# bus-main.net
KiCad netlist of a schematic drawn in Altium Designer
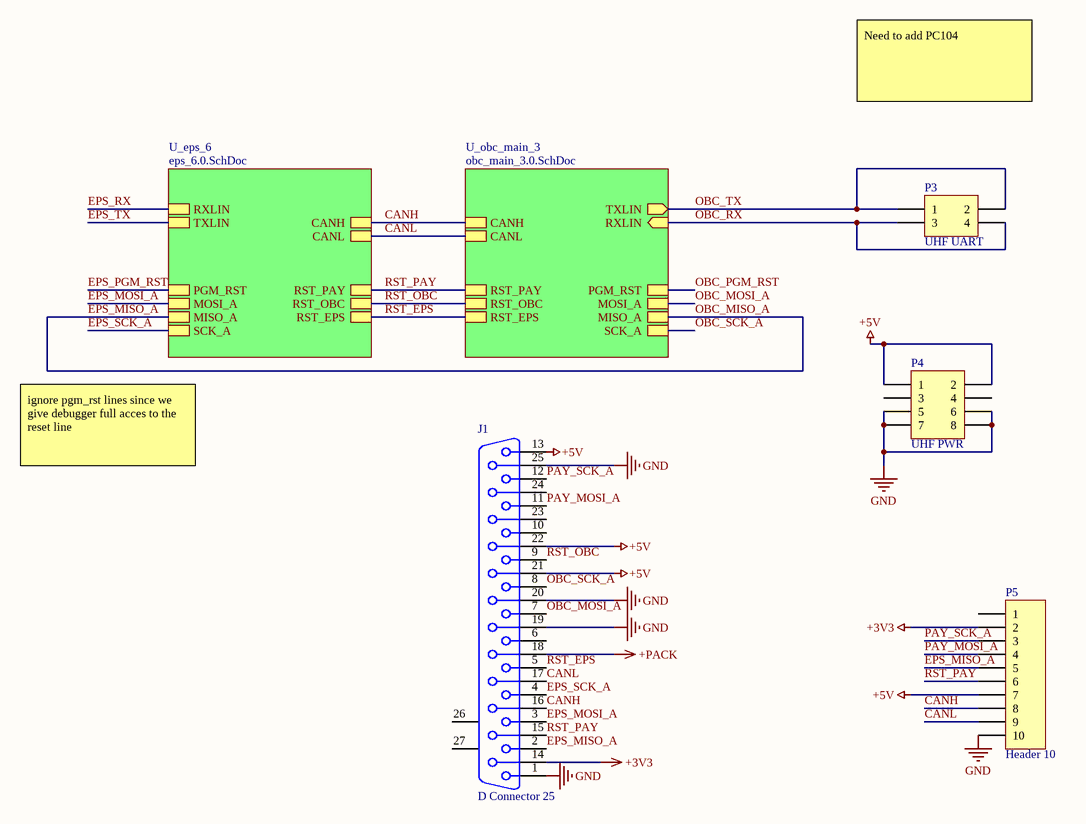
[diagram p0: bus-main.SchDoc]

(export (version "E")
  (design (tool "Eeschema 10.0.6"))
  (components
    (comp (ref "J1")
      (value "D Connector 25")
      (footprint "Mini DSub Connector")
      (description "Receptacle Assembly, 25 Position, Right Angle")
      (fields (field (name "PUBLISHER") "Altium Limited"))
      (libsource (lib "Miscellaneous Connectors") (part "D Connector 25"))
    )
    (comp (ref "P3")
      (value "UHF UART")
      (footprint "HDR2X2")
      (description "Header, 2-Pin, Dual row")
      (fields (field (name "PUBLISHER") "Altium Limited"))
      (libsource (lib "Miscellaneous Connectors") (part "Header 2X2"))
    )
    (comp (ref "P4")
      (value "UHF PWR")
      (footprint "HDR2X4")
      (description "Header, 4-Pin, Dual row")
      (fields (field (name "PUBLISHER") "Altium Limited"))
      (libsource (lib "Miscellaneous Connectors") (part "Header 4X2"))
    )
    (comp (ref "P5")
      (value "Header 10")
      (footprint "DF14-10P-1.25H(55) - duplicate")
      (description "Header, 10-Pin")
      (fields (field (name "PUBLISHER") "Altium Limited"))
      (libsource (lib "Miscellaneous Connectors") (part "Header 10"))
    )
  )
  (nets
    (net (code "1") (name "+3V3") (class "Default")
      (node (ref "J1") (pin "14") (pinfunction "14_14") (pintype "passive"))
      (node (ref "P5") (pin "2") (pinfunction "2_2") (pintype "passive"))
    )
    (net (code "2") (name "+5V") (class "Default")
      (node (ref "J1") (pin "13") (pinfunction "13_13") (pintype "passive"))
      (node (ref "J1") (pin "21") (pinfunction "21_21") (pintype "passive"))
      (node (ref "J1") (pin "22") (pinfunction "22_22") (pintype "passive"))
      (node (ref "P4") (pin "1") (pinfunction "1_1") (pintype "passive"))
      (node (ref "P4") (pin "2") (pinfunction "2_2") (pintype "passive"))
      (node (ref "P5") (pin "7") (pinfunction "7_7") (pintype "passive"))
    )
    (net (code "3") (name "+PACK") (class "Default")
      (node (ref "J1") (pin "18") (pinfunction "18_18") (pintype "passive"))
    )
    (net (code "4") (name "/CANH") (class "Default")
      (node (ref "J1") (pin "16") (pinfunction "16_16") (pintype "passive"))
      (node (ref "P5") (pin "8") (pinfunction "8_8") (pintype "passive"))
    )
    (net (code "5") (name "/CANL") (class "Default")
      (node (ref "J1") (pin "17") (pinfunction "17_17") (pintype "passive"))
      (node (ref "P5") (pin "9") (pinfunction "9_9") (pintype "passive"))
    )
    (net (code "6") (name "/EPS_MISO_A") (class "Default")
      (node (ref "J1") (pin "2") (pinfunction "2_2") (pintype "passive"))
      (node (ref "P5") (pin "5") (pinfunction "5_5") (pintype "passive"))
    )
    (net (code "7") (name "/EPS_MOSI_A") (class "Default")
      (node (ref "J1") (pin "3") (pinfunction "3_3") (pintype "passive"))
    )
    (net (code "10") (name "/EPS_SCK_A") (class "Default")
      (node (ref "J1") (pin "4") (pinfunction "4_4") (pintype "passive"))
    )
    (net (code "12") (name "/OBC_MOSI_A") (class "Default")
      (node (ref "J1") (pin "7") (pinfunction "7_7") (pintype "passive"))
    )
    (net (code "14") (name "/OBC_RX") (class "Default")
      (node (ref "P3") (pin "3") (pinfunction "3_3") (pintype "passive"))
      (node (ref "P3") (pin "4") (pinfunction "4_4") (pintype "passive"))
    )
    (net (code "15") (name "/OBC_SCK_A") (class "Default")
      (node (ref "J1") (pin "8") (pinfunction "8_8") (pintype "passive"))
    )
    (net (code "16") (name "/OBC_TX") (class "Default")
      (node (ref "P3") (pin "1") (pinfunction "1_1") (pintype "passive"))
      (node (ref "P3") (pin "2") (pinfunction "2_2") (pintype "passive"))
    )
    (net (code "17") (name "/PAY_MOSI_A") (class "Default")
      (node (ref "J1") (pin "11") (pinfunction "11_11") (pintype "passive"))
      (node (ref "P5") (pin "4") (pinfunction "4_4") (pintype "passive"))
    )
    (net (code "18") (name "/PAY_SCK_A") (class "Default")
      (node (ref "J1") (pin "12") (pinfunction "12_12") (pintype "passive"))
      (node (ref "P5") (pin "3") (pinfunction "3_3") (pintype "passive"))
    )
    (net (code "19") (name "/RST_EPS") (class "Default")
      (node (ref "J1") (pin "5") (pinfunction "5_5") (pintype "passive"))
    )
    (net (code "20") (name "/RST_OBC") (class "Default")
      (node (ref "J1") (pin "9") (pinfunction "9_9") (pintype "passive"))
    )
    (net (code "21") (name "/RST_PAY") (class "Default")
      (node (ref "J1") (pin "15") (pinfunction "15_15") (pintype "passive"))
      (node (ref "P5") (pin "6") (pinfunction "6_6") (pintype "passive"))
    )
    (net (code "22") (name "GND") (class "Default")
      (node (ref "J1") (pin "1") (pinfunction "1_1") (pintype "passive"))
      (node (ref "J1") (pin "19") (pinfunction "19_19") (pintype "passive"))
      (node (ref "J1") (pin "20") (pinfunction "20_20") (pintype "passive"))
      (node (ref "J1") (pin "25") (pinfunction "25_25") (pintype "passive"))
      (node (ref "P4") (pin "5") (pinfunction "5_5") (pintype "passive"))
      (node (ref "P4") (pin "6") (pinfunction "6_6") (pintype "passive"))
      (node (ref "P4") (pin "7") (pinfunction "7_7") (pintype "passive"))
      (node (ref "P4") (pin "8") (pinfunction "8_8") (pintype "passive"))
      (node (ref "P5") (pin "10") (pinfunction "10_10") (pintype "passive"))
    )
    (net (code "23") (name "unconnected-(J1-MH1-Pad26)") (class "Default")
      (node (ref "J1") (pin "26") (pinfunction "MH1_26") (pintype "passive"))
    )
    (net (code "24") (name "unconnected-(J1-MH2-Pad27)") (class "Default")
      (node (ref "J1") (pin "27") (pinfunction "MH2_27") (pintype "passive"))
    )
    (net (code "25") (name "unconnected-(J1-Pad6)") (class "Default")
      (node (ref "J1") (pin "6") (pinfunction "6_6") (pintype "passive"))
    )
    (net (code "26") (name "unconnected-(J1-Pad10)") (class "Default")
      (node (ref "J1") (pin "10") (pinfunction "10_10") (pintype "passive"))
    )
    (net (code "27") (name "unconnected-(J1-Pad23)") (class "Default")
      (node (ref "J1") (pin "23") (pinfunction "23_23") (pintype "passive"))
    )
    (net (code "28") (name "unconnected-(J1-Pad24)") (class "Default")
      (node (ref "J1") (pin "24") (pinfunction "24_24") (pintype "passive"))
    )
    (net (code "29") (name "unconnected-(P4-Pad3)") (class "Default")
      (node (ref "P4") (pin "3") (pinfunction "3_3") (pintype "passive"))
    )
    (net (code "30") (name "unconnected-(P4-Pad4)") (class "Default")
      (node (ref "P4") (pin "4") (pinfunction "4_4") (pintype "passive"))
    )
    (net (code "31") (name "unconnected-(P5-Pad1)") (class "Default")
      (node (ref "P5") (pin "1") (pinfunction "1_1") (pintype "passive"))
    )
  )
)
